# OttoPi06b-RPi3AHAT.net
KiCad netlist of a schematic drawn in EAGLE
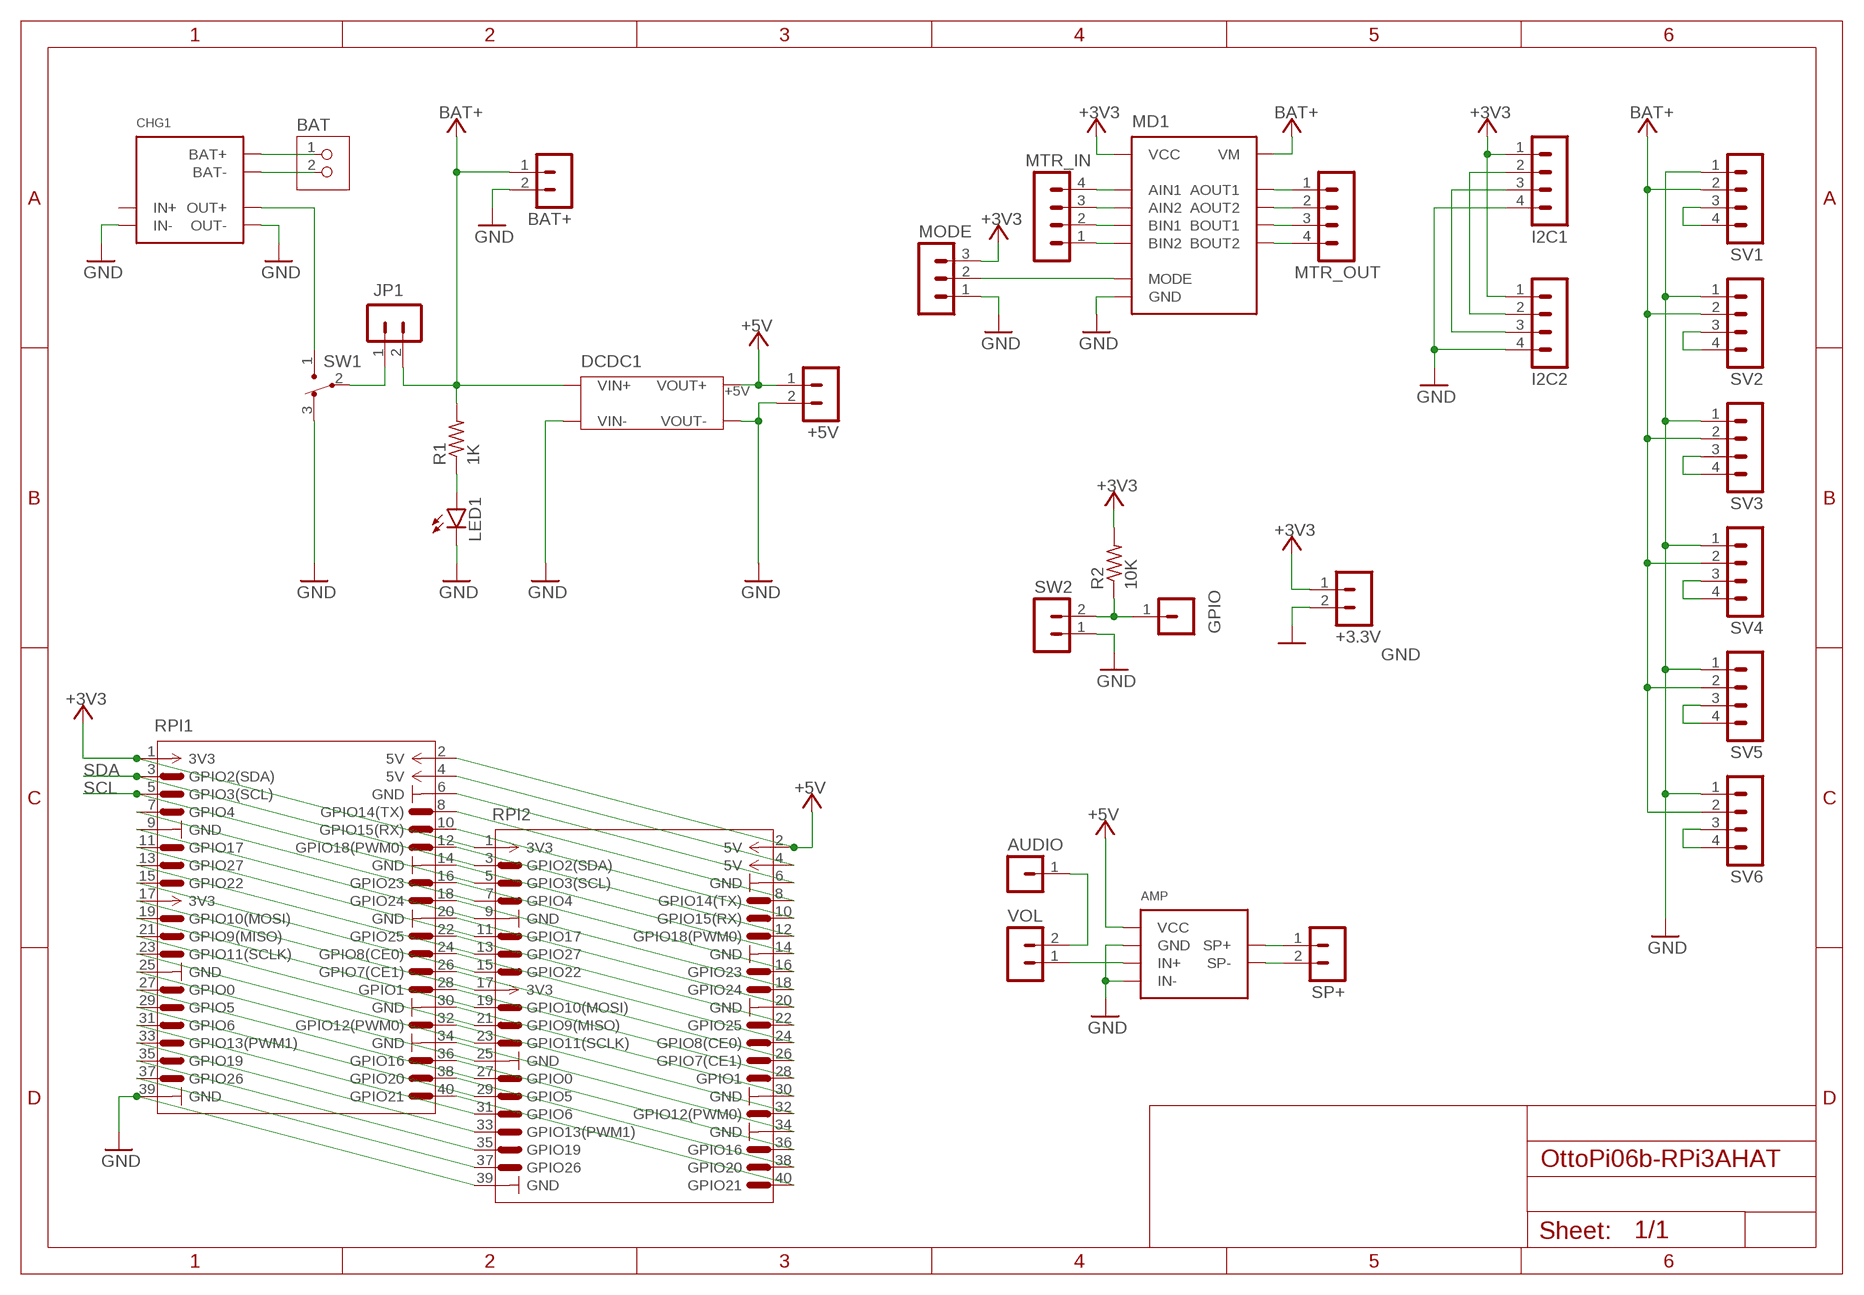
[diagram p0: schematic, sheet 1]

(export (version "E")
  (design (tool "Eeschema 10.0.6"))
  (components
    (comp (ref "+3.3V")
      (value "MA02-1")
      (footprint "eagle-import:MA02-1")
      (libsource (lib "eagle-import") (part "MA02-1"))
    )
    (comp (ref "+5V")
      (value "MA02-1")
      (footprint "eagle-import:MA02-1")
      (libsource (lib "eagle-import") (part "MA02-1"))
    )
    (comp (ref "AMP")
      (value "PAM8012MOD")
      (footprint "eagle-import:PAM8012MOD-A")
      (libsource (lib "eagle-import") (part "PAM8012MOD"))
    )
    (comp (ref "AUDIO")
      (value "MA01-1")
      (footprint "eagle-import:MA01-1")
      (libsource (lib "eagle-import") (part "MA01-1"))
    )
    (comp (ref "BAT")
      (value "JST-PH2")
      (footprint "eagle-import:JST-PH2")
      (libsource (lib "eagle-import") (part "JST-PH2"))
    )
    (comp (ref "BAT+")
      (value "MA02-1")
      (footprint "eagle-import:MA02-1")
      (libsource (lib "eagle-import") (part "MA02-1"))
    )
    (comp (ref "CHG1")
      (value "TP4056MOD1")
      (footprint "eagle-import:TP4056MOD1")
      (libsource (lib "eagle-import") (part "TP4056MOD1"))
    )
    (comp (ref "DCDC1")
      (value "+5V")
      (footprint "eagle-import:DCDC-MT3608-MOD2-USB")
      (libsource (lib "eagle-import") (part "DCDC-MT3608-MODUSB"))
    )
    (comp (ref "GPIO")
      (value "MA01-1")
      (footprint "eagle-import:MA01-1")
      (libsource (lib "eagle-import") (part "MA01-1"))
    )
    (comp (ref "I2C1")
      (value "MA04-1")
      (footprint "eagle-import:MA04-1")
      (libsource (lib "eagle-import") (part "MA04-1"))
    )
    (comp (ref "I2C2")
      (value "MA04-1")
      (footprint "eagle-import:MA04-1")
      (libsource (lib "eagle-import") (part "MA04-1"))
    )
    (comp (ref "JP1")
      (value "MA02-1")
      (footprint "eagle-import:MA02-1")
      (libsource (lib "eagle-import") (part "MA02-1"))
    )
    (comp (ref "LED1")
      (value "LED3MM")
      (footprint "eagle-import:LED3MM")
      (libsource (lib "eagle-import") (part "LED3MM"))
    )
    (comp (ref "MD1")
      (value "DRV8835MOD")
      (footprint "eagle-import:DRV8835MOD")
      (libsource (lib "eagle-import") (part "DRV8835MOD"))
    )
    (comp (ref "MODE")
      (value "MA03-1")
      (footprint "eagle-import:MA03-1")
      (libsource (lib "eagle-import") (part "MA03-1"))
    )
    (comp (ref "MTR_IN")
      (value "MA04-1")
      (footprint "eagle-import:MA04-1")
      (libsource (lib "eagle-import") (part "MA04-1"))
    )
    (comp (ref "MTR_OUT")
      (value "MA04-1")
      (footprint "eagle-import:MA04-1")
      (libsource (lib "eagle-import") (part "MA04-1"))
    )
    (comp (ref "R1")
      (value "1K")
      (footprint "eagle-import:0204_7")
      (libsource (lib "eagle-import") (part "R-US_0204/7"))
    )
    (comp (ref "R2")
      (value "10K")
      (footprint "eagle-import:0204_7")
      (libsource (lib "eagle-import") (part "R-US_0204/7"))
    )
    (comp (ref "RPI1")
      (value "RPI-PIN")
      (footprint "eagle-import:RPI-PIN")
      (libsource (lib "eagle-import") (part "RPI-PIN"))
    )
    (comp (ref "RPI2")
      (value "RPI-PIN")
      (footprint "eagle-import:RPI-PIN")
      (libsource (lib "eagle-import") (part "RPI-PIN"))
    )
    (comp (ref "SP+")
      (value "MA02-1")
      (footprint "eagle-import:MA02-1")
      (libsource (lib "eagle-import") (part "MA02-1"))
    )
    (comp (ref "SV1")
      (value "MA04-1")
      (footprint "eagle-import:MA04-1")
      (libsource (lib "eagle-import") (part "MA04-1"))
    )
    (comp (ref "SV2")
      (value "MA04-1")
      (footprint "eagle-import:MA04-1")
      (libsource (lib "eagle-import") (part "MA04-1"))
    )
    (comp (ref "SV3")
      (value "MA04-1")
      (footprint "eagle-import:MA04-1")
      (libsource (lib "eagle-import") (part "MA04-1"))
    )
    (comp (ref "SV4")
      (value "MA04-1")
      (footprint "eagle-import:MA04-1")
      (libsource (lib "eagle-import") (part "MA04-1"))
    )
    (comp (ref "SV5")
      (value "MA04-1")
      (footprint "eagle-import:MA04-1")
      (libsource (lib "eagle-import") (part "MA04-1"))
    )
    (comp (ref "SV6")
      (value "MA04-1")
      (footprint "eagle-import:MA04-1")
      (libsource (lib "eagle-import") (part "MA04-1"))
    )
    (comp (ref "SW1")
      (value "SW3-1")
      (footprint "eagle-import:SW3-1")
      (fields (field (name "MF") "HiLetgo"))
      (libsource (lib "eagle-import") (part "SW3-1"))
    )
    (comp (ref "SW2")
      (value "MA02-1")
      (footprint "eagle-import:MA02-1")
      (libsource (lib "eagle-import") (part "MA02-1"))
    )
    (comp (ref "VOL")
      (value "MA02-1")
      (footprint "eagle-import:MA02-1")
      (libsource (lib "eagle-import") (part "MA02-1"))
    )
  )
  (nets
    (net (code "1") (name "+3V3") (class "Default")
      (node (ref "+3.3V") (pin "1") (pinfunction "1_1") (pintype "passive"))
      (node (ref "I2C1") (pin "1") (pinfunction "1_1") (pintype "passive"))
      (node (ref "I2C2") (pin "1") (pinfunction "1_1") (pintype "passive"))
      (node (ref "MD1") (pin "VCC") (pinfunction "VCC_VCC") (pintype "input"))
      (node (ref "MODE") (pin "3") (pinfunction "3_3") (pintype "passive"))
      (node (ref "R2") (pin "2") (pinfunction "2_2") (pintype "passive"))
      (node (ref "RPI1") (pin "1") (pinfunction "3V3_1") (pintype "passive"))
      (node (ref "RPI2") (pin "1") (pinfunction "3V3_1") (pintype "passive"))
    )
    (net (code "2") (name "+5V") (class "Default")
      (node (ref "+5V") (pin "1") (pinfunction "1_1") (pintype "passive"))
      (node (ref "AMP") (pin "V+") (pinfunction "VCC_V+") (pintype "passive"))
      (node (ref "DCDC1") (pin "VOUT+") (pinfunction "VOUT+_VOUT+") (pintype "power_in"))
      (node (ref "RPI1") (pin "2") (pinfunction "5V_2") (pintype "passive"))
      (node (ref "RPI2") (pin "2") (pinfunction "5V_2") (pintype "passive"))
    )
    (net (code "3") (name "/SCL") (class "Default")
      (node (ref "I2C1") (pin "3") (pinfunction "3_3") (pintype "passive"))
      (node (ref "I2C2") (pin "3") (pinfunction "3_3") (pintype "passive"))
      (node (ref "RPI1") (pin "5") (pinfunction "GPIO3(SCL)_5") (pintype "passive"))
      (node (ref "RPI2") (pin "5") (pinfunction "GPIO3(SCL)_5") (pintype "passive"))
    )
    (net (code "4") (name "/SDA") (class "Default")
      (node (ref "I2C1") (pin "2") (pinfunction "2_2") (pintype "passive"))
      (node (ref "I2C2") (pin "2") (pinfunction "2_2") (pintype "passive"))
      (node (ref "RPI1") (pin "3") (pinfunction "GPIO2(SDA)_3") (pintype "passive"))
      (node (ref "RPI2") (pin "3") (pinfunction "GPIO2(SDA)_3") (pintype "passive"))
    )
    (net (code "5") (name "BAT+") (class "Default")
      (node (ref "BAT+") (pin "1") (pinfunction "1_1") (pintype "passive"))
      (node (ref "DCDC1") (pin "VIN+") (pinfunction "VIN+_VIN+") (pintype "power_in"))
      (node (ref "JP1") (pin "2") (pinfunction "2_2") (pintype "passive"))
      (node (ref "MD1") (pin "VM") (pinfunction "VM_VM") (pintype "input"))
      (node (ref "R1") (pin "2") (pinfunction "2_2") (pintype "passive"))
      (node (ref "SV1") (pin "2") (pinfunction "2_2") (pintype "passive"))
      (node (ref "SV2") (pin "2") (pinfunction "2_2") (pintype "passive"))
      (node (ref "SV3") (pin "2") (pinfunction "2_2") (pintype "passive"))
      (node (ref "SV4") (pin "2") (pinfunction "2_2") (pintype "passive"))
      (node (ref "SV5") (pin "2") (pinfunction "2_2") (pintype "passive"))
      (node (ref "SV6") (pin "2") (pinfunction "2_2") (pintype "passive"))
    )
    (net (code "6") (name "GND") (class "Default")
      (node (ref "+3.3V") (pin "2") (pinfunction "2_2") (pintype "passive"))
      (node (ref "+5V") (pin "2") (pinfunction "2_2") (pintype "passive"))
      (node (ref "AMP") (pin "GND") (pinfunction "GND_GND") (pintype "passive"))
      (node (ref "AMP") (pin "IN-") (pinfunction "IN-_IN-") (pintype "input"))
      (node (ref "BAT+") (pin "2") (pinfunction "2_2") (pintype "passive"))
      (node (ref "CHG1") (pin "IN-") (pinfunction "IN-_IN-") (pintype "passive"))
      (node (ref "CHG1") (pin "OUT-") (pinfunction "OUT-_OUT-") (pintype "passive"))
      (node (ref "DCDC1") (pin "VIN-") (pinfunction "VIN-_VIN-") (pintype "power_in"))
      (node (ref "DCDC1") (pin "VOUT-") (pinfunction "VOUT-_VOUT-") (pintype "power_in"))
      (node (ref "I2C1") (pin "4") (pinfunction "4_4") (pintype "passive"))
      (node (ref "I2C2") (pin "4") (pinfunction "4_4") (pintype "passive"))
      (node (ref "LED1") (pin "K") (pinfunction "C_K") (pintype "passive"))
      (node (ref "MD1") (pin "GND") (pinfunction "GND_GND") (pintype "power_in"))
      (node (ref "MODE") (pin "1") (pinfunction "1_1") (pintype "passive"))
      (node (ref "RPI1") (pin "39") (pinfunction "GND_39") (pintype "passive"))
      (node (ref "RPI2") (pin "39") (pinfunction "GND_39") (pintype "passive"))
      (node (ref "SV1") (pin "1") (pinfunction "1_1") (pintype "passive"))
      (node (ref "SV2") (pin "1") (pinfunction "1_1") (pintype "passive"))
      (node (ref "SV3") (pin "1") (pinfunction "1_1") (pintype "passive"))
      (node (ref "SV4") (pin "1") (pinfunction "1_1") (pintype "passive"))
      (node (ref "SV5") (pin "1") (pinfunction "1_1") (pintype "passive"))
      (node (ref "SV6") (pin "1") (pinfunction "1_1") (pintype "passive"))
      (node (ref "SW1") (pin "3") (pinfunction "3_3") (pintype "passive"))
      (node (ref "SW2") (pin "1") (pinfunction "1_1") (pintype "passive"))
    )
    (net (code "7") (name "Net-(AMP-PadIN+)") (class "Default")
      (node (ref "AMP") (pin "IN+") (pinfunction "IN+_IN+") (pintype "input"))
      (node (ref "VOL") (pin "1") (pinfunction "1_1") (pintype "passive"))
    )
    (net (code "8") (name "Net-(AMP-SP+)") (class "Default")
      (node (ref "AMP") (pin "SP+@1") (pinfunction "SP+_SP+@1") (pintype "output"))
      (node (ref "SP+") (pin "1") (pinfunction "1_1") (pintype "passive"))
    )
    (net (code "9") (name "Net-(AMP-SP-)") (class "Default")
      (node (ref "AMP") (pin "SP-@1") (pinfunction "SP-_SP-@1") (pintype "output"))
      (node (ref "SP+") (pin "2") (pinfunction "2_2") (pintype "passive"))
    )
    (net (code "10") (name "Net-(AUDIO-Pad1)") (class "Default")
      (node (ref "AUDIO") (pin "1") (pinfunction "1_1") (pintype "passive"))
      (node (ref "VOL") (pin "2") (pinfunction "2_2") (pintype "passive"))
    )
    (net (code "11") (name "Net-(BAT-Pad1)") (class "Default")
      (node (ref "BAT") (pin "1") (pinfunction "1_1") (pintype "passive"))
      (node (ref "CHG1") (pin "BAT+") (pinfunction "BAT+_BAT+") (pintype "passive"))
    )
    (net (code "12") (name "Net-(BAT-Pad2)") (class "Default")
      (node (ref "BAT") (pin "2") (pinfunction "2_2") (pintype "passive"))
      (node (ref "CHG1") (pin "BAT-") (pinfunction "BAT-_BAT-") (pintype "passive"))
    )
    (net (code "13") (name "Net-(CHG1-PadOUT+)") (class "Default")
      (node (ref "CHG1") (pin "OUT+") (pinfunction "OUT+_OUT+") (pintype "passive"))
      (node (ref "SW1") (pin "1") (pinfunction "1_1") (pintype "passive"))
    )
    (net (code "14") (name "Net-(GPIO-Pad1)") (class "Default")
      (node (ref "GPIO") (pin "1") (pinfunction "1_1") (pintype "passive"))
      (node (ref "R2") (pin "1") (pinfunction "1_1") (pintype "passive"))
      (node (ref "SW2") (pin "2") (pinfunction "2_2") (pintype "passive"))
    )
    (net (code "15") (name "Net-(JP1-Pad1)") (class "Default")
      (node (ref "JP1") (pin "1") (pinfunction "1_1") (pintype "passive"))
      (node (ref "SW1") (pin "2") (pinfunction "2_2") (pintype "passive"))
    )
    (net (code "16") (name "Net-(LED1-PadA)") (class "Default")
      (node (ref "LED1") (pin "A") (pinfunction "A_A") (pintype "passive"))
      (node (ref "R1") (pin "1") (pinfunction "1_1") (pintype "passive"))
    )
    (net (code "17") (name "Net-(MD1-PadAIN1)") (class "Default")
      (node (ref "MD1") (pin "AIN1") (pinfunction "AIN1_AIN1") (pintype "input"))
      (node (ref "MTR_IN") (pin "4") (pinfunction "4_4") (pintype "passive"))
    )
    (net (code "18") (name "Net-(MD1-PadAIN2)") (class "Default")
      (node (ref "MD1") (pin "AIN2") (pinfunction "AIN2_AIN2") (pintype "input"))
      (node (ref "MTR_IN") (pin "3") (pinfunction "3_3") (pintype "passive"))
    )
    (net (code "19") (name "Net-(MD1-PadAOUT1)") (class "Default")
      (node (ref "MD1") (pin "AOUT1") (pinfunction "AOUT1_AOUT1") (pintype "output"))
      (node (ref "MTR_OUT") (pin "1") (pinfunction "1_1") (pintype "passive"))
    )
    (net (code "20") (name "Net-(MD1-PadAOUT2)") (class "Default")
      (node (ref "MD1") (pin "AOUT2") (pinfunction "AOUT2_AOUT2") (pintype "output"))
      (node (ref "MTR_OUT") (pin "2") (pinfunction "2_2") (pintype "passive"))
    )
    (net (code "21") (name "Net-(MD1-PadBIN1)") (class "Default")
      (node (ref "MD1") (pin "BIN1") (pinfunction "BIN1_BIN1") (pintype "input"))
      (node (ref "MTR_IN") (pin "2") (pinfunction "2_2") (pintype "passive"))
    )
    (net (code "22") (name "Net-(MD1-PadBIN2)") (class "Default")
      (node (ref "MD1") (pin "BIN2") (pinfunction "BIN2_BIN2") (pintype "input"))
      (node (ref "MTR_IN") (pin "1") (pinfunction "1_1") (pintype "passive"))
    )
    (net (code "23") (name "Net-(MD1-PadBOUT1)") (class "Default")
      (node (ref "MD1") (pin "BOUT1") (pinfunction "BOUT1_BOUT1") (pintype "output"))
      (node (ref "MTR_OUT") (pin "3") (pinfunction "3_3") (pintype "passive"))
    )
    (net (code "24") (name "Net-(MD1-PadBOUT2)") (class "Default")
      (node (ref "MD1") (pin "BOUT2") (pinfunction "BOUT2_BOUT2") (pintype "output"))
      (node (ref "MTR_OUT") (pin "4") (pinfunction "4_4") (pintype "passive"))
    )
    (net (code "25") (name "Net-(MD1-PadMODE)") (class "Default")
      (node (ref "MD1") (pin "MODE") (pinfunction "MODE_MODE") (pintype "input"))
      (node (ref "MODE") (pin "2") (pinfunction "2_2") (pintype "passive"))
    )
    (net (code "26") (name "Net-(RPI1-3V3-Pad17)") (class "Default")
      (node (ref "RPI1") (pin "17") (pinfunction "3V3_17") (pintype "passive"))
      (node (ref "RPI2") (pin "17") (pinfunction "3V3_17") (pintype "passive"))
    )
    (net (code "27") (name "Net-(RPI1-5V-Pad4)") (class "Default")
      (node (ref "RPI1") (pin "4") (pinfunction "5V_4") (pintype "passive"))
      (node (ref "RPI2") (pin "4") (pinfunction "5V_4") (pintype "passive"))
    )
    (net (code "28") (name "Net-(RPI1-GND-Pad6)") (class "Default")
      (node (ref "RPI1") (pin "6") (pinfunction "GND_6") (pintype "passive"))
      (node (ref "RPI2") (pin "6") (pinfunction "GND_6") (pintype "passive"))
    )
    (net (code "29") (name "Net-(RPI1-GND-Pad9)") (class "Default")
      (node (ref "RPI1") (pin "9") (pinfunction "GND_9") (pintype "passive"))
      (node (ref "RPI2") (pin "9") (pinfunction "GND_9") (pintype "passive"))
    )
    (net (code "30") (name "Net-(RPI1-GND-Pad14)") (class "Default")
      (node (ref "RPI1") (pin "14") (pinfunction "GND_14") (pintype "passive"))
      (node (ref "RPI2") (pin "14") (pinfunction "GND_14") (pintype "passive"))
    )
    (net (code "31") (name "Net-(RPI1-GND-Pad20)") (class "Default")
      (node (ref "RPI1") (pin "20") (pinfunction "GND_20") (pintype "passive"))
      (node (ref "RPI2") (pin "20") (pinfunction "GND_20") (pintype "passive"))
    )
    (net (code "32") (name "Net-(RPI1-GND-Pad25)") (class "Default")
      (node (ref "RPI1") (pin "25") (pinfunction "GND_25") (pintype "passive"))
      (node (ref "RPI2") (pin "25") (pinfunction "GND_25") (pintype "passive"))
    )
    (net (code "33") (name "Net-(RPI1-GND-Pad30)") (class "Default")
      (node (ref "RPI1") (pin "30") (pinfunction "GND_30") (pintype "passive"))
      (node (ref "RPI2") (pin "30") (pinfunction "GND_30") (pintype "passive"))
    )
    (net (code "34") (name "Net-(RPI1-GND-Pad34)") (class "Default")
      (node (ref "RPI1") (pin "34") (pinfunction "GND_34") (pintype "passive"))
      (node (ref "RPI2") (pin "34") (pinfunction "GND_34") (pintype "passive"))
    )
    (net (code "35") (name "Net-(RPI1-GPIO0)") (class "Default")
      (node (ref "RPI1") (pin "27") (pinfunction "GPIO0_27") (pintype "passive"))
      (node (ref "RPI2") (pin "27") (pinfunction "GPIO0_27") (pintype "passive"))
    )
    (net (code "36") (name "Net-(RPI1-GPIO1)") (class "Default")
      (node (ref "RPI1") (pin "28") (pinfunction "GPIO1_28") (pintype "passive"))
      (node (ref "RPI2") (pin "28") (pinfunction "GPIO1_28") (pintype "passive"))
    )
    (net (code "37") (name "Net-(RPI1-GPIO4)") (class "Default")
      (node (ref "RPI1") (pin "7") (pinfunction "GPIO4_7") (pintype "passive"))
      (node (ref "RPI2") (pin "7") (pinfunction "GPIO4_7") (pintype "passive"))
    )
    (net (code "38") (name "Net-(RPI1-GPIO5)") (class "Default")
      (node (ref "RPI1") (pin "29") (pinfunction "GPIO5_29") (pintype "passive"))
      (node (ref "RPI2") (pin "29") (pinfunction "GPIO5_29") (pintype "passive"))
    )
    (net (code "39") (name "Net-(RPI1-GPIO6)") (class "Default")
      (node (ref "RPI1") (pin "31") (pinfunction "GPIO6_31") (pintype "passive"))
      (node (ref "RPI2") (pin "31") (pinfunction "GPIO6_31") (pintype "passive"))
    )
    (net (code "40") (name "Net-(RPI1-GPIO7(CE1))") (class "Default")
      (node (ref "RPI1") (pin "26") (pinfunction "GPIO7(CE1)_26") (pintype "passive"))
      (node (ref "RPI2") (pin "26") (pinfunction "GPIO7(CE1)_26") (pintype "passive"))
    )
    (net (code "41") (name "Net-(RPI1-GPIO8(CE0))") (class "Default")
      (node (ref "RPI1") (pin "24") (pinfunction "GPIO8(CE0)_24") (pintype "passive"))
      (node (ref "RPI2") (pin "24") (pinfunction "GPIO8(CE0)_24") (pintype "passive"))
    )
    (net (code "42") (name "Net-(RPI1-GPIO9(MISO))") (class "Default")
      (node (ref "RPI1") (pin "21") (pinfunction "GPIO9(MISO)_21") (pintype "passive"))
      (node (ref "RPI2") (pin "21") (pinfunction "GPIO9(MISO)_21") (pintype "passive"))
    )
    (net (code "43") (name "Net-(RPI1-GPIO10(MOSI))") (class "Default")
      (node (ref "RPI1") (pin "19") (pinfunction "GPIO10(MOSI)_19") (pintype "passive"))
      (node (ref "RPI2") (pin "19") (pinfunction "GPIO10(MOSI)_19") (pintype "passive"))
    )
    (net (code "44") (name "Net-(RPI1-GPIO11(SCLK))") (class "Default")
      (node (ref "RPI1") (pin "23") (pinfunction "GPIO11(SCLK)_23") (pintype "passive"))
      (node (ref "RPI2") (pin "23") (pinfunction "GPIO11(SCLK)_23") (pintype "passive"))
    )
    (net (code "45") (name "Net-(RPI1-GPIO12(PWM0))") (class "Default")
      (node (ref "RPI1") (pin "32") (pinfunction "GPIO12(PWM0)_32") (pintype "passive"))
      (node (ref "RPI2") (pin "32") (pinfunction "GPIO12(PWM0)_32") (pintype "passive"))
    )
    (net (code "46") (name "Net-(RPI1-GPIO13(PWM1))") (class "Default")
      (node (ref "RPI1") (pin "33") (pinfunction "GPIO13(PWM1)_33") (pintype "passive"))
      (node (ref "RPI2") (pin "33") (pinfunction "GPIO13(PWM1)_33") (pintype "passive"))
    )
    (net (code "47") (name "Net-(RPI1-GPIO14(TX))") (class "Default")
      (node (ref "RPI1") (pin "8") (pinfunction "GPIO14(TX)_8") (pintype "passive"))
      (node (ref "RPI2") (pin "8") (pinfunction "GPIO14(TX)_8") (pintype "passive"))
    )
    (net (code "48") (name "Net-(RPI1-GPIO15(RX))") (class "Default")
      (node (ref "RPI1") (pin "10") (pinfunction "GPIO15(RX)_10") (pintype "passive"))
      (node (ref "RPI2") (pin "10") (pinfunction "GPIO15(RX)_10") (pintype "passive"))
    )
    (net (code "49") (name "Net-(RPI1-GPIO16)") (class "Default")
      (node (ref "RPI1") (pin "36") (pinfunction "GPIO16_36") (pintype "passive"))
      (node (ref "RPI2") (pin "36") (pinfunction "GPIO16_36") (pintype "passive"))
    )
    (net (code "50") (name "Net-(RPI1-GPIO17)") (class "Default")
      (node (ref "RPI1") (pin "11") (pinfunction "GPIO17_11") (pintype "passive"))
      (node (ref "RPI2") (pin "11") (pinfunction "GPIO17_11") (pintype "passive"))
    )
    (net (code "51") (name "Net-(RPI1-GPIO18(PWM0))") (class "Default")
      (node (ref "RPI1") (pin "12") (pinfunction "GPIO18(PWM0)_12") (pintype "passive"))
      (node (ref "RPI2") (pin "12") (pinfunction "GPIO18(PWM0)_12") (pintype "passive"))
    )
    (net (code "52") (name "Net-(RPI1-GPIO19)") (class "Default")
      (node (ref "RPI1") (pin "35") (pinfunction "GPIO19_35") (pintype "passive"))
      (node (ref "RPI2") (pin "35") (pinfunction "GPIO19_35") (pintype "passive"))
    )
    (net (code "53") (name "Net-(RPI1-GPIO20)") (class "Default")
      (node (ref "RPI1") (pin "38") (pinfunction "GPIO20_38") (pintype "passive"))
      (node (ref "RPI2") (pin "38") (pinfunction "GPIO20_38") (pintype "passive"))
    )
    (net (code "54") (name "Net-(RPI1-GPIO21)") (class "Default")
      (node (ref "RPI1") (pin "40") (pinfunction "GPIO21_40") (pintype "passive"))
      (node (ref "RPI2") (pin "40") (pinfunction "GPIO21_40") (pintype "passive"))
    )
    (net (code "55") (name "Net-(RPI1-GPIO22)") (class "Default")
      (node (ref "RPI1") (pin "15") (pinfunction "GPIO22_15") (pintype "passive"))
      (node (ref "RPI2") (pin "15") (pinfunction "GPIO22_15") (pintype "passive"))
    )
    (net (code "56") (name "Net-(RPI1-GPIO23)") (class "Default")
      (node (ref "RPI1") (pin "16") (pinfunction "GPIO23_16") (pintype "passive"))
      (node (ref "RPI2") (pin "16") (pinfunction "GPIO23_16") (pintype "passive"))
    )
    (net (code "57") (name "Net-(RPI1-GPIO24)") (class "Default")
      (node (ref "RPI1") (pin "18") (pinfunction "GPIO24_18") (pintype "passive"))
      (node (ref "RPI2") (pin "18") (pinfunction "GPIO24_18") (pintype "passive"))
    )
    (net (code "58") (name "Net-(RPI1-GPIO25)") (class "Default")
      (node (ref "RPI1") (pin "22") (pinfunction "GPIO25_22") (pintype "passive"))
      (node (ref "RPI2") (pin "22") (pinfunction "GPIO25_22") (pintype "passive"))
    )
    (net (code "59") (name "Net-(RPI1-GPIO26)") (class "Default")
      (node (ref "RPI1") (pin "37") (pinfunction "GPIO26_37") (pintype "passive"))
      (node (ref "RPI2") (pin "37") (pinfunction "GPIO26_37") (pintype "passive"))
    )
    (net (code "60") (name "Net-(RPI1-GPIO27)") (class "Default")
      (node (ref "RPI1") (pin "13") (pinfunction "GPIO27_13") (pintype "passive"))
      (node (ref "RPI2") (pin "13") (pinfunction "GPIO27_13") (pintype "passive"))
    )
    (net (code "61") (name "Net-(SV1-Pad3)") (class "Default")
      (node (ref "SV1") (pin "3") (pinfunction "3_3") (pintype "passive"))
      (node (ref "SV1") (pin "4") (pinfunction "4_4") (pintype "passive"))
    )
    (net (code "62") (name "Net-(SV2-Pad3)") (class "Default")
      (node (ref "SV2") (pin "3") (pinfunction "3_3") (pintype "passive"))
      (node (ref "SV2") (pin "4") (pinfunction "4_4") (pintype "passive"))
    )
    (net (code "63") (name "Net-(SV3-Pad3)") (class "Default")
      (node (ref "SV3") (pin "3") (pinfunction "3_3") (pintype "passive"))
      (node (ref "SV3") (pin "4") (pinfunction "4_4") (pintype "passive"))
    )
    (net (code "64") (name "Net-(SV4-Pad3)") (class "Default")
      (node (ref "SV4") (pin "3") (pinfunction "3_3") (pintype "passive"))
      (node (ref "SV4") (pin "4") (pinfunction "4_4") (pintype "passive"))
    )
    (net (code "65") (name "Net-(SV5-Pad3)") (class "Default")
      (node (ref "SV5") (pin "3") (pinfunction "3_3") (pintype "passive"))
      (node (ref "SV5") (pin "4") (pinfunction "4_4") (pintype "passive"))
    )
    (net (code "66") (name "Net-(SV6-Pad3)") (class "Default")
      (node (ref "SV6") (pin "3") (pinfunction "3_3") (pintype "passive"))
      (node (ref "SV6") (pin "4") (pinfunction "4_4") (pintype "passive"))
    )
    (net (code "67") (name "unconnected-(CHG1-PadIN+)") (class "Default")
      (node (ref "CHG1") (pin "IN+") (pinfunction "IN+_IN+") (pintype "passive"))
    )
  )
)
